# Sheet1.net
KiCad netlist of a schematic drawn in Altium Designer
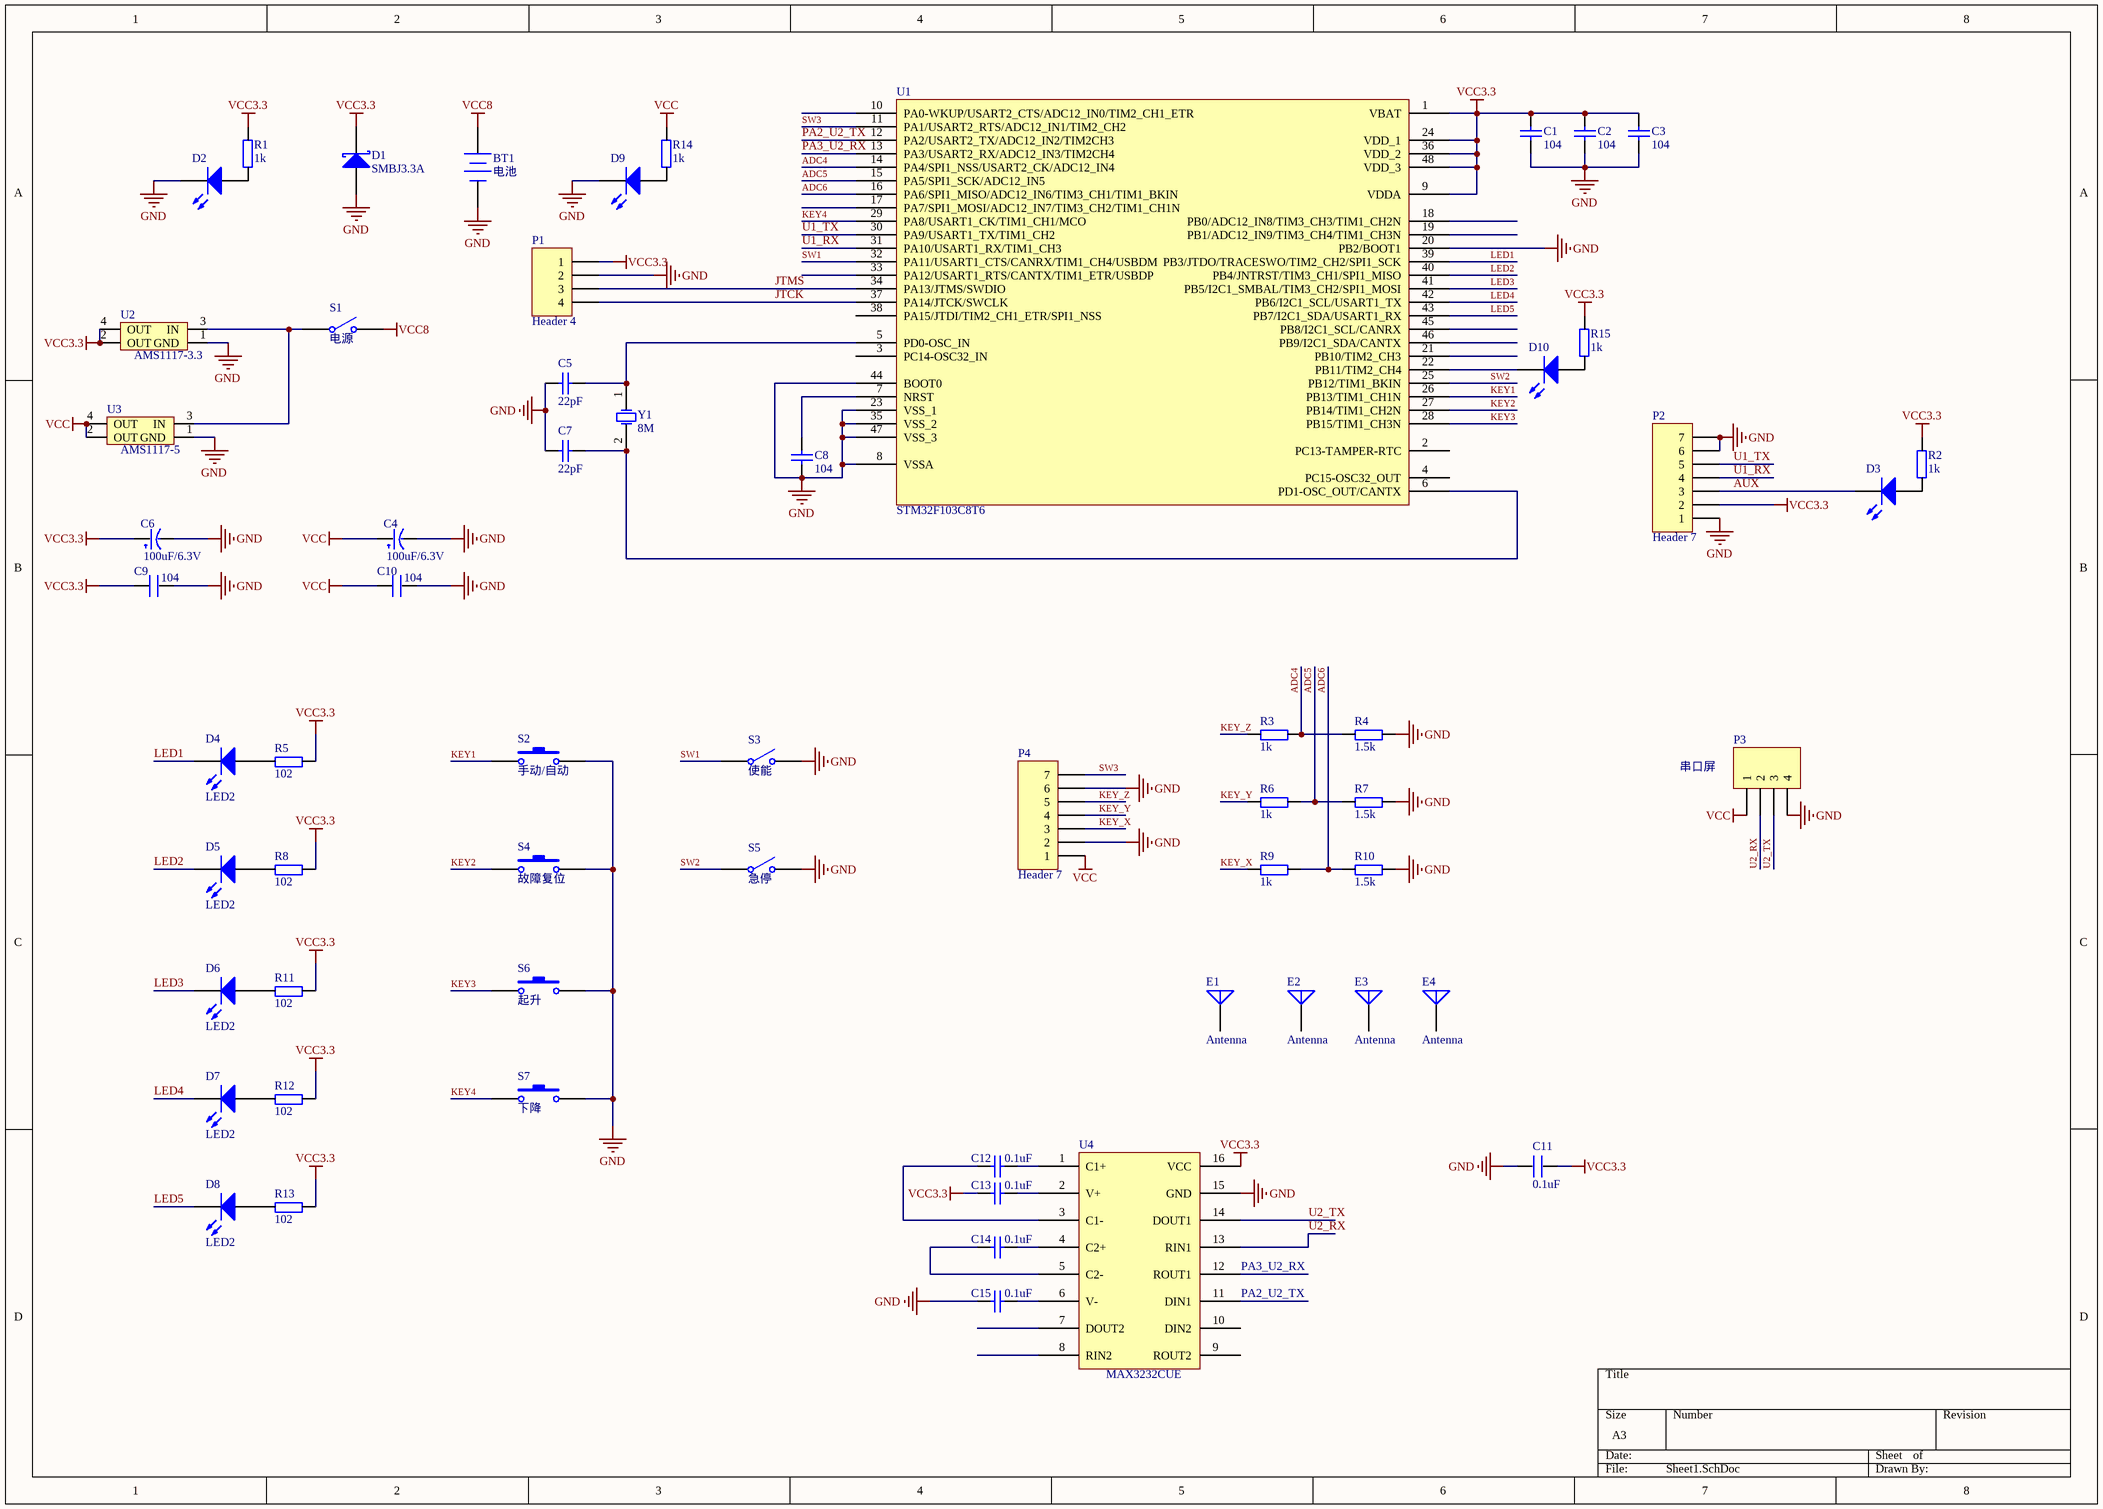
[diagram p0: Sheet1.SchDoc]

(export (version "E")
  (design (tool "Eeschema 10.0.6"))
  (components
    (comp (ref "BT1")
      (value "电池")
      (footprint "KEY/SW")
      (description "Multicell Battery")
      (fields (field (name "PUBLISHER") "Altium Limited"))
      (libsource (lib "Miscellaneous Devices") (part "Battery"))
    )
    (comp (ref "C1")
      (value "104")
      (footprint "0805_C")
      (description "Capacitor")
      (fields (field (name "PUBLISHER") "Altium Limited"))
      (libsource (lib "Miscellaneous Devices") (part "Cap"))
    )
    (comp (ref "C2")
      (value "104")
      (footprint "0805_C")
      (description "Capacitor")
      (fields (field (name "PUBLISHER") "Altium Limited"))
      (libsource (lib "Miscellaneous Devices") (part "Cap"))
    )
    (comp (ref "C3")
      (value "104")
      (footprint "0805_C")
      (description "Capacitor")
      (fields (field (name "PUBLISHER") "Altium Limited"))
      (libsource (lib "Miscellaneous Devices") (part "Cap"))
    )
    (comp (ref "C4") (value "100uF/6.3V") (footprint "3216") (libsource (lib "WarShip V3_SCH") (part "CAP")))
    (comp (ref "C5")
      (value "22pF")
      (footprint "0805_C")
      (description "Capacitor")
      (fields (field (name "PUBLISHER") "Altium Limited"))
      (libsource (lib "Miscellaneous Devices") (part "Cap"))
    )
    (comp (ref "C6") (value "100uF/6.3V") (footprint "3216") (libsource (lib "WarShip V3_SCH") (part "CAP")))
    (comp (ref "C7")
      (value "22pF")
      (footprint "0805_C")
      (description "Capacitor")
      (fields (field (name "PUBLISHER") "Altium Limited"))
      (libsource (lib "Miscellaneous Devices") (part "Cap"))
    )
    (comp (ref "C8")
      (value "104")
      (footprint "0805_C")
      (description "Capacitor")
      (fields (field (name "PUBLISHER") "Altium Limited"))
      (libsource (lib "Miscellaneous Devices") (part "Cap"))
    )
    (comp (ref "C9") (value "104") (footprint "0805_C") (libsource (lib "WarShip V3_SCH") (part "C")))
    (comp (ref "C10") (value "104") (footprint "0805_C") (libsource (lib "WarShip V3_SCH") (part "C")))
    (comp (ref "C11")
      (value "0.1uF")
      (footprint "0805_C")
      (libsource (lib "Explorer STM32F407封装库") (part "C_2"))
    )
    (comp (ref "C12")
      (value "0.1uF")
      (footprint "0805_C")
      (description "Capacitor")
      (fields (field (name "PUBLISHER") "Altium Limited"))
      (libsource (lib "Miscellaneous Devices") (part "Cap"))
    )
    (comp (ref "C13")
      (value "0.1uF")
      (footprint "0805_C")
      (description "Capacitor")
      (fields (field (name "PUBLISHER") "Altium Limited"))
      (libsource (lib "Miscellaneous Devices") (part "Cap"))
    )
    (comp (ref "C14")
      (value "0.1uF")
      (footprint "0805_C")
      (description "Capacitor")
      (fields (field (name "PUBLISHER") "Altium Limited"))
      (libsource (lib "Miscellaneous Devices") (part "Cap"))
    )
    (comp (ref "C15")
      (value "0.1uF")
      (footprint "0805_C")
      (description "Capacitor")
      (fields (field (name "PUBLISHER") "Altium Limited"))
      (libsource (lib "Miscellaneous Devices") (part "Cap"))
    )
    (comp (ref "D1")
      (value "SMBJ3.3A")
      (footprint "SMB(DO-214AA)_S1")
      (description "Schottky Rectifier")
      (fields (field (name "PUBLISHER") "Altium Limited"))
      (libsource (lib "Miscellaneous Devices") (part "Diode 18TQ045"))
    )
    (comp (ref "D2")
      (value "LED0")
      (footprint "LC-0805_LED_S1")
      (description "Typical INFRARED GaAs LED")
      (fields (field (name "PUBLISHER") "Altium Limited"))
      (libsource (lib "继电器板_1") (part "LED0"))
    )
    (comp (ref "D3")
      (value "LED0")
      (footprint "LC-0805_LED_S1")
      (description "Typical INFRARED GaAs LED")
      (fields (field (name "PUBLISHER") "Altium Limited"))
      (libsource (lib "继电器板_1") (part "LED0"))
    )
    (comp (ref "D4")
      (value "LED2")
      (footprint "LED1")
      (description "Typical RED, GREEN, YELLOW, AMBER GaAs LED")
      (fields (field (name "PUBLISHER") "Altium Limited"))
      (libsource (lib "Miscellaneous Devices") (part "LED2"))
    )
    (comp (ref "D5")
      (value "LED2")
      (footprint "LED1")
      (description "Typical RED, GREEN, YELLOW, AMBER GaAs LED")
      (fields (field (name "PUBLISHER") "Altium Limited"))
      (libsource (lib "Miscellaneous Devices") (part "LED2"))
    )
    (comp (ref "D6")
      (value "LED2")
      (footprint "LED1")
      (description "Typical RED, GREEN, YELLOW, AMBER GaAs LED")
      (fields (field (name "PUBLISHER") "Altium Limited"))
      (libsource (lib "Miscellaneous Devices") (part "LED2"))
    )
    (comp (ref "D7")
      (value "LED2")
      (footprint "LED1")
      (description "Typical RED, GREEN, YELLOW, AMBER GaAs LED")
      (fields (field (name "PUBLISHER") "Altium Limited"))
      (libsource (lib "Miscellaneous Devices") (part "LED2"))
    )
    (comp (ref "D8")
      (value "LED2")
      (footprint "LED1")
      (description "Typical RED, GREEN, YELLOW, AMBER GaAs LED")
      (fields (field (name "PUBLISHER") "Altium Limited"))
      (libsource (lib "Miscellaneous Devices") (part "LED2"))
    )
    (comp (ref "D9")
      (value "LED0")
      (footprint "LC-0805_LED_S1")
      (description "Typical INFRARED GaAs LED")
      (fields (field (name "PUBLISHER") "Altium Limited"))
      (libsource (lib "继电器板_1") (part "LED0"))
    )
    (comp (ref "D10")
      (value "LED0")
      (footprint "LC-0805_LED_S1")
      (description "Typical INFRARED GaAs LED")
      (fields (field (name "PUBLISHER") "Altium Limited"))
      (libsource (lib "继电器板_1") (part "LED0"))
    )
    (comp (ref "E1")
      (value "Antenna")
      (footprint "定位孔 Φ3.2")
      (description "Generic Antenna")
      (fields (field (name "PUBLISHER") "Altium Limited"))
      (libsource (lib "Miscellaneous Devices") (part "Antenna"))
    )
    (comp (ref "E2")
      (value "Antenna")
      (footprint "定位孔 Φ3.2")
      (description "Generic Antenna")
      (fields (field (name "PUBLISHER") "Altium Limited"))
      (libsource (lib "Miscellaneous Devices") (part "Antenna"))
    )
    (comp (ref "E3")
      (value "Antenna")
      (footprint "定位孔 Φ3.2")
      (description "Generic Antenna")
      (fields (field (name "PUBLISHER") "Altium Limited"))
      (libsource (lib "Miscellaneous Devices") (part "Antenna"))
    )
    (comp (ref "E4")
      (value "Antenna")
      (footprint "定位孔 Φ3.2")
      (description "Generic Antenna")
      (fields (field (name "PUBLISHER") "Altium Limited"))
      (libsource (lib "Miscellaneous Devices") (part "Antenna"))
    )
    (comp (ref "P1")
      (value "Header 4")
      (footprint "IDE4")
      (description "Header, 4-Pin")
      (fields (field (name "PUBLISHER") "Altium Limited"))
      (libsource (lib "") (part "Header 4_1"))
    )
    (comp (ref "P2")
      (value "Header 7")
      (footprint "AS50-T27")
      (description "Header, 7-Pin")
      (fields (field (name "PUBLISHER") "Altium Limited"))
      (libsource (lib "Miscellaneous Connectors") (part "Header 7"))
    )
    (comp (ref "P3")
      (value "串口屏")
      (footprint "IDE4")
      (description "Header, 4-Pin")
      (fields (field (name "PUBLISHER") "Altium Limited"))
      (libsource (lib "Miscellaneous Connectors") (part "Header 4"))
    )
    (comp (ref "P4")
      (value "Header 7")
      (footprint "HDR1X7")
      (description "Header, 7-Pin")
      (fields (field (name "PUBLISHER") "Altium Limited"))
      (libsource (lib "Miscellaneous Connectors") (part "Header 7"))
    )
    (comp (ref "R1") (value "1k") (footprint "0603_R") (libsource (lib "Explorer STM32F407封装库") (part "R_2")))
    (comp (ref "R2") (value "1k") (footprint "0603_R") (libsource (lib "Explorer STM32F407封装库") (part "R_2")))
    (comp (ref "R3") (value "1k") (footprint "0603_R") (libsource (lib "Explorer STM32F407封装库") (part "R_2")))
    (comp (ref "R4")
      (value "1.5k")
      (footprint "0603_R")
      (libsource (lib "Explorer STM32F407封装库") (part "R_2"))
    )
    (comp (ref "R5")
      (value "102")
      (footprint "0603_R")
      (libsource (lib "Explorer STM32F407封装库") (part "R_2"))
    )
    (comp (ref "R6") (value "1k") (footprint "0603_R") (libsource (lib "Explorer STM32F407封装库") (part "R_2")))
    (comp (ref "R7")
      (value "1.5k")
      (footprint "0603_R")
      (libsource (lib "Explorer STM32F407封装库") (part "R_2"))
    )
    (comp (ref "R8")
      (value "102")
      (footprint "0603_R")
      (libsource (lib "Explorer STM32F407封装库") (part "R_2"))
    )
    (comp (ref "R9") (value "1k") (footprint "0603_R") (libsource (lib "Explorer STM32F407封装库") (part "R_2")))
    (comp (ref "R10")
      (value "1.5k")
      (footprint "0603_R")
      (libsource (lib "Explorer STM32F407封装库") (part "R_2"))
    )
    (comp (ref "R11")
      (value "102")
      (footprint "0603_R")
      (libsource (lib "Explorer STM32F407封装库") (part "R_2"))
    )
    (comp (ref "R12")
      (value "102")
      (footprint "0603_R")
      (libsource (lib "Explorer STM32F407封装库") (part "R_2"))
    )
    (comp (ref "R13")
      (value "102")
      (footprint "0603_R")
      (libsource (lib "Explorer STM32F407封装库") (part "R_2"))
    )
    (comp (ref "R14")
      (value "1k")
      (footprint "0603_R")
      (libsource (lib "Explorer STM32F407封装库") (part "R_2"))
    )
    (comp (ref "R15")
      (value "1k")
      (footprint "0603_R")
      (libsource (lib "Explorer STM32F407封装库") (part "R_2"))
    )
    (comp (ref "S1")
      (value "电源")
      (footprint "KEY/SW")
      (description "Single-Pole, Single-Throw Switch")
      (fields (field (name "PUBLISHER") "Altium Limited"))
      (libsource (lib "Miscellaneous Devices") (part "SW-SPST"))
    )
    (comp (ref "S2")
      (value "手动/自动")
      (footprint "KEY/SW")
      (description "Switch")
      (fields (field (name "PUBLISHER") "Altium Limited"))
      (libsource (lib "Miscellaneous Devices") (part "SW-PB"))
    )
    (comp (ref "S3")
      (value "使能")
      (footprint "KEY/SW")
      (description "Single-Pole, Single-Throw Switch")
      (fields (field (name "PUBLISHER") "Altium Limited"))
      (libsource (lib "Miscellaneous Devices") (part "SW-SPST"))
    )
    (comp (ref "S4")
      (value "故障复位")
      (footprint "KEY/SW")
      (description "Switch")
      (fields (field (name "PUBLISHER") "Altium Limited"))
      (libsource (lib "Miscellaneous Devices") (part "SW-PB"))
    )
    (comp (ref "S5")
      (value "急停")
      (footprint "KEY/SW")
      (description "Single-Pole, Single-Throw Switch")
      (fields (field (name "PUBLISHER") "Altium Limited"))
      (libsource (lib "Miscellaneous Devices") (part "SW-SPST"))
    )
    (comp (ref "S6")
      (value "起升")
      (footprint "KEY/SW")
      (description "Switch")
      (fields (field (name "PUBLISHER") "Altium Limited"))
      (libsource (lib "Miscellaneous Devices") (part "SW-PB"))
    )
    (comp (ref "S7")
      (value "下降")
      (footprint "KEY/SW")
      (description "Switch")
      (fields (field (name "PUBLISHER") "Altium Limited"))
      (libsource (lib "Miscellaneous Devices") (part "SW-PB"))
    )
    (comp (ref "U1")
      (value "STM32F103C8T6")
      (footprint "LQFP-48_7x7x05P")
      (libsource (lib "Schlib1") (part "stm32f103v8t6"))
    )
    (comp (ref "U2")
      (value "AMS1117-3.3")
      (footprint "LC-SOT-223")
      (libsource (lib "WarShip V3_SCH") (part "AMS1117"))
    )
    (comp (ref "U3")
      (value "AMS1117-5")
      (footprint "LC-SOT-223")
      (libsource (lib "WarShip V3_SCH") (part "AMS1117"))
    )
    (comp (ref "U4")
      (value "MAX3232CUE")
      (footprint "SO-16")
      (libsource (lib "Smart_board_v1") (part "MAX3232CUE"))
    )
    (comp (ref "Y1")
      (value "8M")
      (footprint "XTAL_US")
      (description "Crystal Oscillator")
      (fields (field (name "PUBLISHER") "Altium Limited"))
      (libsource (lib "Miscellaneous Devices") (part "XTAL"))
    )
  )
  (nets
    (net (code "1") (name "/ADC4") (class "Default")
      (node (ref "R3") (pin "2") (pintype "passive"))
      (node (ref "R4") (pin "1") (pintype "passive"))
      (node (ref "U1") (pin "14") (pinfunction "PA4/SPI1_NSS/USART2_CK/ADC12_IN4_14") (pintype "passive"))
    )
    (net (code "2") (name "/ADC5") (class "Default")
      (node (ref "R6") (pin "2") (pintype "passive"))
      (node (ref "R7") (pin "1") (pintype "passive"))
      (node (ref "U1") (pin "15") (pinfunction "PA5/SPI1_SCK/ADC12_IN5_15") (pintype "passive"))
    )
    (net (code "3") (name "/ADC6") (class "Default")
      (node (ref "R10") (pin "1") (pintype "passive"))
      (node (ref "R9") (pin "2") (pintype "passive"))
      (node (ref "U1") (pin "16") (pinfunction "PA6/SPI1_MISO/ADC12_IN6/TIM3_CH1/TIM1_BKIN_16") (pintype "passive"))
    )
    (net (code "4") (name "/AUX") (class "Default")
      (node (ref "D3") (pin "K") (pinfunction "K_K") (pintype "passive"))
      (node (ref "P2") (pin "3") (pinfunction "3_3") (pintype "passive"))
    )
    (net (code "5") (name "/JTCK") (class "Default")
      (node (ref "P1") (pin "4") (pinfunction "4_4") (pintype "passive"))
      (node (ref "U1") (pin "37") (pinfunction "PA14/JTCK/SWCLK_37") (pintype "passive"))
    )
    (net (code "6") (name "/JTMS") (class "Default")
      (node (ref "P1") (pin "3") (pinfunction "3_3") (pintype "passive"))
      (node (ref "U1") (pin "34") (pinfunction "PA13/JTMS/SWDIO_34") (pintype "passive"))
    )
    (net (code "7") (name "/KEY1") (class "Default")
      (node (ref "S2") (pin "1") (pinfunction "1_1") (pintype "passive"))
      (node (ref "U1") (pin "26") (pinfunction "PB13/TIM1_CH1N_26") (pintype "passive"))
    )
    (net (code "8") (name "/KEY2") (class "Default")
      (node (ref "S4") (pin "1") (pinfunction "1_1") (pintype "passive"))
      (node (ref "U1") (pin "27") (pinfunction "PB14/TIM1_CH2N_27") (pintype "passive"))
    )
    (net (code "9") (name "/KEY3") (class "Default")
      (node (ref "S6") (pin "1") (pinfunction "1_1") (pintype "passive"))
      (node (ref "U1") (pin "28") (pinfunction "PB15/TIM1_CH3N_28") (pintype "passive"))
    )
    (net (code "10") (name "/KEY4") (class "Default")
      (node (ref "S7") (pin "1") (pinfunction "1_1") (pintype "passive"))
      (node (ref "U1") (pin "29") (pinfunction "PA8/USART1_CK/TIM1_CH1/MCO_29") (pintype "passive"))
    )
    (net (code "11") (name "/KEY_X") (class "Default")
      (node (ref "P4") (pin "3") (pinfunction "3_3") (pintype "passive"))
      (node (ref "R9") (pin "1") (pintype "passive"))
    )
    (net (code "12") (name "/KEY_Y") (class "Default")
      (node (ref "P4") (pin "4") (pinfunction "4_4") (pintype "passive"))
      (node (ref "R6") (pin "1") (pintype "passive"))
    )
    (net (code "13") (name "/KEY_Z") (class "Default")
      (node (ref "P4") (pin "5") (pinfunction "5_5") (pintype "passive"))
      (node (ref "R3") (pin "1") (pintype "passive"))
    )
    (net (code "14") (name "/LED1") (class "Default")
      (node (ref "D4") (pin "2") (pinfunction "K_2") (pintype "passive"))
      (node (ref "U1") (pin "39") (pinfunction "PB3/JTDO/TRACESWO/TIM2_CH2/SPI1_SCK_39") (pintype "passive"))
    )
    (net (code "15") (name "/LED2") (class "Default")
      (node (ref "D5") (pin "2") (pinfunction "K_2") (pintype "passive"))
      (node (ref "U1") (pin "40") (pinfunction "PB4/JNTRST/TIM3_CH1/SPI1_MISO_40") (pintype "passive"))
    )
    (net (code "16") (name "/LED3") (class "Default")
      (node (ref "D6") (pin "2") (pinfunction "K_2") (pintype "passive"))
      (node (ref "U1") (pin "41") (pinfunction "PB5/I2C1_SMBAL/TIM3_CH2/SPI1_MOSI_41") (pintype "passive"))
    )
    (net (code "17") (name "/LED4") (class "Default")
      (node (ref "D7") (pin "2") (pinfunction "K_2") (pintype "passive"))
      (node (ref "U1") (pin "42") (pinfunction "PB6/I2C1_SCL/USART1_TX_42") (pintype "passive"))
    )
    (net (code "18") (name "/LED5") (class "Default")
      (node (ref "D8") (pin "2") (pinfunction "K_2") (pintype "passive"))
      (node (ref "U1") (pin "43") (pinfunction "PB7/I2C1_SDA/USART1_RX_43") (pintype "passive"))
    )
    (net (code "19") (name "/PA2_U2_TX") (class "Default")
      (node (ref "U1") (pin "12") (pinfunction "PA2/USART2_TX/ADC12_IN2/TIM2CH3_12") (pintype "passive"))
      (node (ref "U4") (pin "11") (pinfunction "DIN1_11") (pintype "passive"))
    )
    (net (code "20") (name "/PA3_U2_RX") (class "Default")
      (node (ref "U1") (pin "13") (pinfunction "PA3/USART2_RX/ADC12_IN3/TIM2CH4_13") (pintype "passive"))
      (node (ref "U4") (pin "12") (pinfunction "ROUT1_12") (pintype "passive"))
    )
    (net (code "21") (name "/SW1") (class "Default")
      (node (ref "S3") (pin "1") (pinfunction "COMMON_1") (pintype "passive"))
      (node (ref "U1") (pin "32") (pinfunction "PA11/USART1_CTS/CANRX/TIM1_CH4/USBDM_32") (pintype "passive"))
    )
    (net (code "22") (name "/SW2") (class "Default")
      (node (ref "S5") (pin "1") (pinfunction "COMMON_1") (pintype "passive"))
      (node (ref "U1") (pin "25") (pinfunction "PB12/TIM1_BKIN_25") (pintype "passive"))
    )
    (net (code "23") (name "/SW3") (class "Default")
      (node (ref "P4") (pin "7") (pinfunction "7_7") (pintype "passive"))
      (node (ref "U1") (pin "11") (pinfunction "PA1/USART2_RTS/ADC12_IN1/TIM2_CH2_11") (pintype "passive"))
    )
    (net (code "24") (name "/U1_RX") (class "Default")
      (node (ref "P2") (pin "4") (pinfunction "4_4") (pintype "passive"))
      (node (ref "U1") (pin "31") (pinfunction "PA10/USART1_RX/TIM1_CH3_31") (pintype "passive"))
    )
    (net (code "25") (name "/U1_TX") (class "Default")
      (node (ref "P2") (pin "5") (pinfunction "5_5") (pintype "passive"))
      (node (ref "U1") (pin "30") (pinfunction "PA9/USART1_TX/TIM1_CH2_30") (pintype "passive"))
    )
    (net (code "26") (name "/U2_RX") (class "Default")
      (node (ref "P3") (pin "2") (pinfunction "2_2") (pintype "passive"))
      (node (ref "U4") (pin "13") (pinfunction "RIN1_13") (pintype "passive"))
    )
    (net (code "27") (name "/U2_TX") (class "Default")
      (node (ref "P3") (pin "3") (pinfunction "3_3") (pintype "passive"))
      (node (ref "U4") (pin "14") (pinfunction "DOUT1_14") (pintype "passive"))
    )
    (net (code "28") (name "GND") (class "Default")
      (node (ref "BT1") (pin "2") (pinfunction "-_2") (pintype "passive"))
      (node (ref "C1") (pin "2") (pinfunction "2_2") (pintype "passive"))
      (node (ref "C10") (pin "1") (pintype "passive"))
      (node (ref "C11") (pin "1") (pintype "passive"))
      (node (ref "C15") (pin "2") (pinfunction "2_2") (pintype "passive"))
      (node (ref "C2") (pin "2") (pinfunction "2_2") (pintype "passive"))
      (node (ref "C3") (pin "2") (pinfunction "2_2") (pintype "passive"))
      (node (ref "C4") (pin "2") (pinfunction "GND_2") (pintype "passive"))
      (node (ref "C5") (pin "2") (pinfunction "2_2") (pintype "passive"))
      (node (ref "C6") (pin "2") (pinfunction "GND_2") (pintype "passive"))
      (node (ref "C7") (pin "2") (pinfunction "2_2") (pintype "passive"))
      (node (ref "C8") (pin "2") (pinfunction "2_2") (pintype "passive"))
      (node (ref "C9") (pin "1") (pintype "passive"))
      (node (ref "D1") (pin "2") (pinfunction "A_2") (pintype "passive"))
      (node (ref "D2") (pin "K") (pinfunction "K_K") (pintype "passive"))
      (node (ref "D9") (pin "K") (pinfunction "K_K") (pintype "passive"))
      (node (ref "P1") (pin "2") (pinfunction "2_2") (pintype "passive"))
      (node (ref "P2") (pin "1") (pinfunction "1_1") (pintype "passive"))
      (node (ref "P2") (pin "6") (pinfunction "6_6") (pintype "passive"))
      (node (ref "P2") (pin "7") (pinfunction "7_7") (pintype "passive"))
      (node (ref "P3") (pin "4") (pinfunction "4_4") (pintype "passive"))
      (node (ref "P4") (pin "2") (pinfunction "2_2") (pintype "passive"))
      (node (ref "P4") (pin "6") (pinfunction "6_6") (pintype "passive"))
      (node (ref "R10") (pin "2") (pintype "passive"))
      (node (ref "R4") (pin "2") (pintype "passive"))
      (node (ref "R7") (pin "2") (pintype "passive"))
      (node (ref "S2") (pin "2") (pinfunction "2_2") (pintype "passive"))
      (node (ref "S3") (pin "2") (pinfunction "NO_2") (pintype "passive"))
      (node (ref "S4") (pin "2") (pinfunction "2_2") (pintype "passive"))
      (node (ref "S5") (pin "2") (pinfunction "NO_2") (pintype "passive"))
      (node (ref "S6") (pin "2") (pinfunction "2_2") (pintype "passive"))
      (node (ref "S7") (pin "2") (pinfunction "2_2") (pintype "passive"))
      (node (ref "U1") (pin "20") (pinfunction "PB2/BOOT1_20") (pintype "passive"))
      (node (ref "U1") (pin "23") (pinfunction "VSS_1_23") (pintype "passive"))
      (node (ref "U1") (pin "35") (pinfunction "VSS_2_35") (pintype "passive"))
      (node (ref "U1") (pin "44") (pinfunction "BOOT0_44") (pintype "passive"))
      (node (ref "U1") (pin "47") (pinfunction "VSS_3_47") (pintype "passive"))
      (node (ref "U1") (pin "8") (pinfunction "VSSA_8") (pintype "passive"))
      (node (ref "U2") (pin "1") (pinfunction "GND_1") (pintype "passive"))
      (node (ref "U3") (pin "1") (pinfunction "GND_1") (pintype "passive"))
      (node (ref "U4") (pin "15") (pinfunction "GND_15") (pintype "passive"))
    )
    (net (code "29") (name "Net-(D2-PadA)") (class "Default")
      (node (ref "D2") (pin "A") (pinfunction "A_A") (pintype "passive"))
      (node (ref "R1") (pin "2") (pintype "passive"))
    )
    (net (code "30") (name "Net-(D3-PadA)") (class "Default")
      (node (ref "D3") (pin "A") (pinfunction "A_A") (pintype "passive"))
      (node (ref "R2") (pin "2") (pintype "passive"))
    )
    (net (code "31") (name "Net-(D4-A)") (class "Default")
      (node (ref "D4") (pin "1") (pinfunction "A_1") (pintype "passive"))
      (node (ref "R5") (pin "1") (pintype "passive"))
    )
    (net (code "32") (name "Net-(D5-A)") (class "Default")
      (node (ref "D5") (pin "1") (pinfunction "A_1") (pintype "passive"))
      (node (ref "R8") (pin "1") (pintype "passive"))
    )
    (net (code "33") (name "Net-(D6-A)") (class "Default")
      (node (ref "D6") (pin "1") (pinfunction "A_1") (pintype "passive"))
      (node (ref "R11") (pin "1") (pintype "passive"))
    )
    (net (code "34") (name "Net-(D7-A)") (class "Default")
      (node (ref "D7") (pin "1") (pinfunction "A_1") (pintype "passive"))
      (node (ref "R12") (pin "1") (pintype "passive"))
    )
    (net (code "35") (name "Net-(D8-A)") (class "Default")
      (node (ref "D8") (pin "1") (pinfunction "A_1") (pintype "passive"))
      (node (ref "R13") (pin "1") (pintype "passive"))
    )
    (net (code "36") (name "Net-(D9-PadA)") (class "Default")
      (node (ref "D9") (pin "A") (pinfunction "A_A") (pintype "passive"))
      (node (ref "R14") (pin "2") (pintype "passive"))
    )
    (net (code "37") (name "Net-(D10-PadA)") (class "Default")
      (node (ref "D10") (pin "A") (pinfunction "A_A") (pintype "passive"))
      (node (ref "R15") (pin "2") (pintype "passive"))
    )
    (net (code "38") (name "Net-(S1-COMMON)") (class "Default")
      (node (ref "S1") (pin "1") (pinfunction "COMMON_1") (pintype "passive"))
      (node (ref "U2") (pin "3") (pinfunction "IN_3") (pintype "passive"))
      (node (ref "U3") (pin "3") (pinfunction "IN_3") (pintype "passive"))
    )
    (net (code "39") (name "Net-(U1-NRST)") (class "Default")
      (node (ref "C8") (pin "1") (pinfunction "1_1") (pintype "passive"))
      (node (ref "U1") (pin "7") (pinfunction "NRST_7") (pintype "passive"))
    )
    (net (code "40") (name "Net-(U1-PB11{slash}TIM2_CH4)") (class "Default")
      (node (ref "D10") (pin "K") (pinfunction "K_K") (pintype "passive"))
      (node (ref "U1") (pin "22") (pinfunction "PB11/TIM2_CH4_22") (pintype "passive"))
    )
    (net (code "41") (name "Net-(U1-PD0-OSC_IN)") (class "Default")
      (node (ref "C5") (pin "1") (pinfunction "1_1") (pintype "passive"))
      (node (ref "U1") (pin "5") (pinfunction "PD0-OSC_IN_5") (pintype "passive"))
      (node (ref "Y1") (pin "1") (pinfunction "OSC1_1") (pintype "passive"))
    )
    (net (code "42") (name "Net-(U1-PD1-OSC_OUT{slash}CANTX)") (class "Default")
      (node (ref "C7") (pin "1") (pinfunction "1_1") (pintype "passive"))
      (node (ref "U1") (pin "6") (pinfunction "PD1-OSC_OUT/CANTX_6") (pintype "passive"))
      (node (ref "Y1") (pin "2") (pinfunction "OSC2_2") (pintype "passive"))
    )
    (net (code "43") (name "Net-(U4-C1+)") (class "Default")
      (node (ref "C12") (pin "1") (pinfunction "1_1") (pintype "passive"))
      (node (ref "U4") (pin "1") (pinfunction "C1+_1") (pintype "passive"))
    )
    (net (code "44") (name "Net-(U4-C1-)") (class "Default")
      (node (ref "C12") (pin "2") (pinfunction "2_2") (pintype "passive"))
      (node (ref "U4") (pin "3") (pinfunction "C1-_3") (pintype "passive"))
    )
    (net (code "45") (name "Net-(U4-C2+)") (class "Default")
      (node (ref "C14") (pin "1") (pinfunction "1_1") (pintype "passive"))
      (node (ref "U4") (pin "4") (pinfunction "C2+_4") (pintype "passive"))
    )
    (net (code "46") (name "Net-(U4-C2-)") (class "Default")
      (node (ref "C14") (pin "2") (pinfunction "2_2") (pintype "passive"))
      (node (ref "U4") (pin "5") (pinfunction "C2-_5") (pintype "passive"))
    )
    (net (code "47") (name "Net-(U4-V+)") (class "Default")
      (node (ref "C13") (pin "1") (pinfunction "1_1") (pintype "passive"))
      (node (ref "U4") (pin "2") (pinfunction "V+_2") (pintype "passive"))
    )
    (net (code "48") (name "Net-(U4-V-)") (class "Default")
      (node (ref "C15") (pin "1") (pinfunction "1_1") (pintype "passive"))
      (node (ref "U4") (pin "6") (pinfunction "V-_6") (pintype "passive"))
    )
    (net (code "49") (name "VCC") (class "Default")
      (node (ref "C10") (pin "2") (pintype "passive"))
      (node (ref "C4") (pin "1") (pinfunction "VCC_1") (pintype "passive"))
      (node (ref "P3") (pin "1") (pinfunction "1_1") (pintype "passive"))
      (node (ref "P4") (pin "1") (pinfunction "1_1") (pintype "passive"))
      (node (ref "R14") (pin "1") (pintype "passive"))
      (node (ref "U3") (pin "2") (pinfunction "OUT_2") (pintype "passive"))
      (node (ref "U3") (pin "4") (pinfunction "OUT_4") (pintype "passive"))
    )
    (net (code "50") (name "VCC3.3") (class "Default")
      (node (ref "C1") (pin "1") (pinfunction "1_1") (pintype "passive"))
      (node (ref "C11") (pin "2") (pintype "passive"))
      (node (ref "C13") (pin "2") (pinfunction "2_2") (pintype "passive"))
      (node (ref "C2") (pin "1") (pinfunction "1_1") (pintype "passive"))
      (node (ref "C3") (pin "1") (pinfunction "1_1") (pintype "passive"))
      (node (ref "C6") (pin "1") (pinfunction "VCC_1") (pintype "passive"))
      (node (ref "C9") (pin "2") (pintype "passive"))
      (node (ref "D1") (pin "1") (pinfunction "K_1") (pintype "passive"))
      (node (ref "P1") (pin "1") (pinfunction "1_1") (pintype "passive"))
      (node (ref "P2") (pin "2") (pinfunction "2_2") (pintype "passive"))
      (node (ref "R1") (pin "1") (pintype "passive"))
      (node (ref "R11") (pin "2") (pintype "passive"))
      (node (ref "R12") (pin "2") (pintype "passive"))
      (node (ref "R13") (pin "2") (pintype "passive"))
      (node (ref "R15") (pin "1") (pintype "passive"))
      (node (ref "R2") (pin "1") (pintype "passive"))
      (node (ref "R5") (pin "2") (pintype "passive"))
      (node (ref "R8") (pin "2") (pintype "passive"))
      (node (ref "U1") (pin "1") (pinfunction "VBAT_1") (pintype "passive"))
      (node (ref "U1") (pin "24") (pinfunction "VDD_1_24") (pintype "passive"))
      (node (ref "U1") (pin "36") (pinfunction "VDD_2_36") (pintype "passive"))
      (node (ref "U1") (pin "48") (pinfunction "VDD_3_48") (pintype "passive"))
      (node (ref "U1") (pin "9") (pinfunction "VDDA_9") (pintype "passive"))
      (node (ref "U2") (pin "2") (pinfunction "OUT_2") (pintype "passive"))
      (node (ref "U2") (pin "4") (pinfunction "OUT_4") (pintype "passive"))
      (node (ref "U4") (pin "16") (pinfunction "VCC_16") (pintype "passive"))
    )
    (net (code "51") (name "VCC8") (class "Default")
      (node (ref "BT1") (pin "1") (pinfunction "+_1") (pintype "passive"))
      (node (ref "S1") (pin "2") (pinfunction "NO_2") (pintype "passive"))
    )
    (net (code "52") (name "unconnected-(E1-A-Pad1)") (class "Default")
      (node (ref "E1") (pin "1") (pinfunction "A_1") (pintype "passive"))
    )
    (net (code "53") (name "unconnected-(E2-A-Pad1)") (class "Default")
      (node (ref "E2") (pin "1") (pinfunction "A_1") (pintype "passive"))
    )
    (net (code "54") (name "unconnected-(E3-A-Pad1)") (class "Default")
      (node (ref "E3") (pin "1") (pinfunction "A_1") (pintype "passive"))
    )
    (net (code "55") (name "unconnected-(E4-A-Pad1)") (class "Default")
      (node (ref "E4") (pin "1") (pinfunction "A_1") (pintype "passive"))
    )
    (net (code "56") (name "unconnected-(U1-PA0-WKUP{slash}USART2_CTS{slash}ADC12_IN0{slash}TIM2_CH1_ETR-Pad10)") (class "Default")
      (node (ref "U1") (pin "10") (pinfunction "PA0-WKUP/USART2_CTS/ADC12_IN0/TIM2_CH1_ETR_10") (pintype "passive"))
    )
    (net (code "57") (name "unconnected-(U1-PA7{slash}SPI1_MOSI{slash}ADC12_IN7{slash}TIM3_CH2{slash}TIM1_CH1N-Pad17)") (class "Default")
      (node (ref "U1") (pin "17") (pinfunction "PA7/SPI1_MOSI/ADC12_IN7/TIM3_CH2/TIM1_CH1N_17") (pintype "passive"))
    )
    (net (code "58") (name "unconnected-(U1-PA12{slash}USART1_RTS{slash}CANTX{slash}TIM1_ETR{slash}USBDP-Pad33)") (class "Default")
      (node (ref "U1") (pin "33") (pinfunction "PA12/USART1_RTS/CANTX/TIM1_ETR/USBDP_33") (pintype "passive"))
    )
    (net (code "59") (name "unconnected-(U1-PA15{slash}JTDI{slash}TIM2_CH1_ETR{slash}SPI1_NSS-Pad38)") (class "Default")
      (node (ref "U1") (pin "38") (pinfunction "PA15/JTDI/TIM2_CH1_ETR/SPI1_NSS_38") (pintype "passive"))
    )
    (net (code "60") (name "unconnected-(U1-PB0{slash}ADC12_IN8{slash}TIM3_CH3{slash}TIM1_CH2N-Pad18)") (class "Default")
      (node (ref "U1") (pin "18") (pinfunction "PB0/ADC12_IN8/TIM3_CH3/TIM1_CH2N_18") (pintype "passive"))
    )
    (net (code "61") (name "unconnected-(U1-PB1{slash}ADC12_IN9{slash}TIM3_CH4{slash}TIM1_CH3N-Pad19)") (class "Default")
      (node (ref "U1") (pin "19") (pinfunction "PB1/ADC12_IN9/TIM3_CH4/TIM1_CH3N_19") (pintype "passive"))
    )
    (net (code "62") (name "unconnected-(U1-PB8{slash}I2C1_SCL{slash}CANRX-Pad45)") (class "Default")
      (node (ref "U1") (pin "45") (pinfunction "PB8/I2C1_SCL/CANRX_45") (pintype "passive"))
    )
    (net (code "63") (name "unconnected-(U1-PB9{slash}I2C1_SDA{slash}CANTX-Pad46)") (class "Default")
      (node (ref "U1") (pin "46") (pinfunction "PB9/I2C1_SDA/CANTX_46") (pintype "passive"))
    )
    (net (code "64") (name "unconnected-(U1-PB10{slash}TIM2_CH3-Pad21)") (class "Default")
      (node (ref "U1") (pin "21") (pinfunction "PB10/TIM2_CH3_21") (pintype "passive"))
    )
    (net (code "65") (name "unconnected-(U1-PC13-TAMPER-RTC-Pad2)") (class "Default")
      (node (ref "U1") (pin "2") (pinfunction "PC13-TAMPER-RTC_2") (pintype "passive"))
    )
    (net (code "66") (name "unconnected-(U1-PC14-OSC32_IN-Pad3)") (class "Default")
      (node (ref "U1") (pin "3") (pinfunction "PC14-OSC32_IN_3") (pintype "passive"))
    )
    (net (code "67") (name "unconnected-(U1-PC15-OSC32_OUT-Pad4)") (class "Default")
      (node (ref "U1") (pin "4") (pinfunction "PC15-OSC32_OUT_4") (pintype "passive"))
    )
    (net (code "68") (name "unconnected-(U4-DIN2-Pad10)") (class "Default")
      (node (ref "U4") (pin "10") (pinfunction "DIN2_10") (pintype "passive"))
    )
    (net (code "69") (name "unconnected-(U4-DOUT2-Pad7)") (class "Default")
      (node (ref "U4") (pin "7") (pinfunction "DOUT2_7") (pintype "passive"))
    )
    (net (code "70") (name "unconnected-(U4-RIN2-Pad8)") (class "Default")
      (node (ref "U4") (pin "8") (pinfunction "RIN2_8") (pintype "passive"))
    )
    (net (code "71") (name "unconnected-(U4-ROUT2-Pad9)") (class "Default")
      (node (ref "U4") (pin "9") (pinfunction "ROUT2_9") (pintype "passive"))
    )
  )
)
